# PCB_4.net
KiCad netlist of a schematic drawn in EAGLE
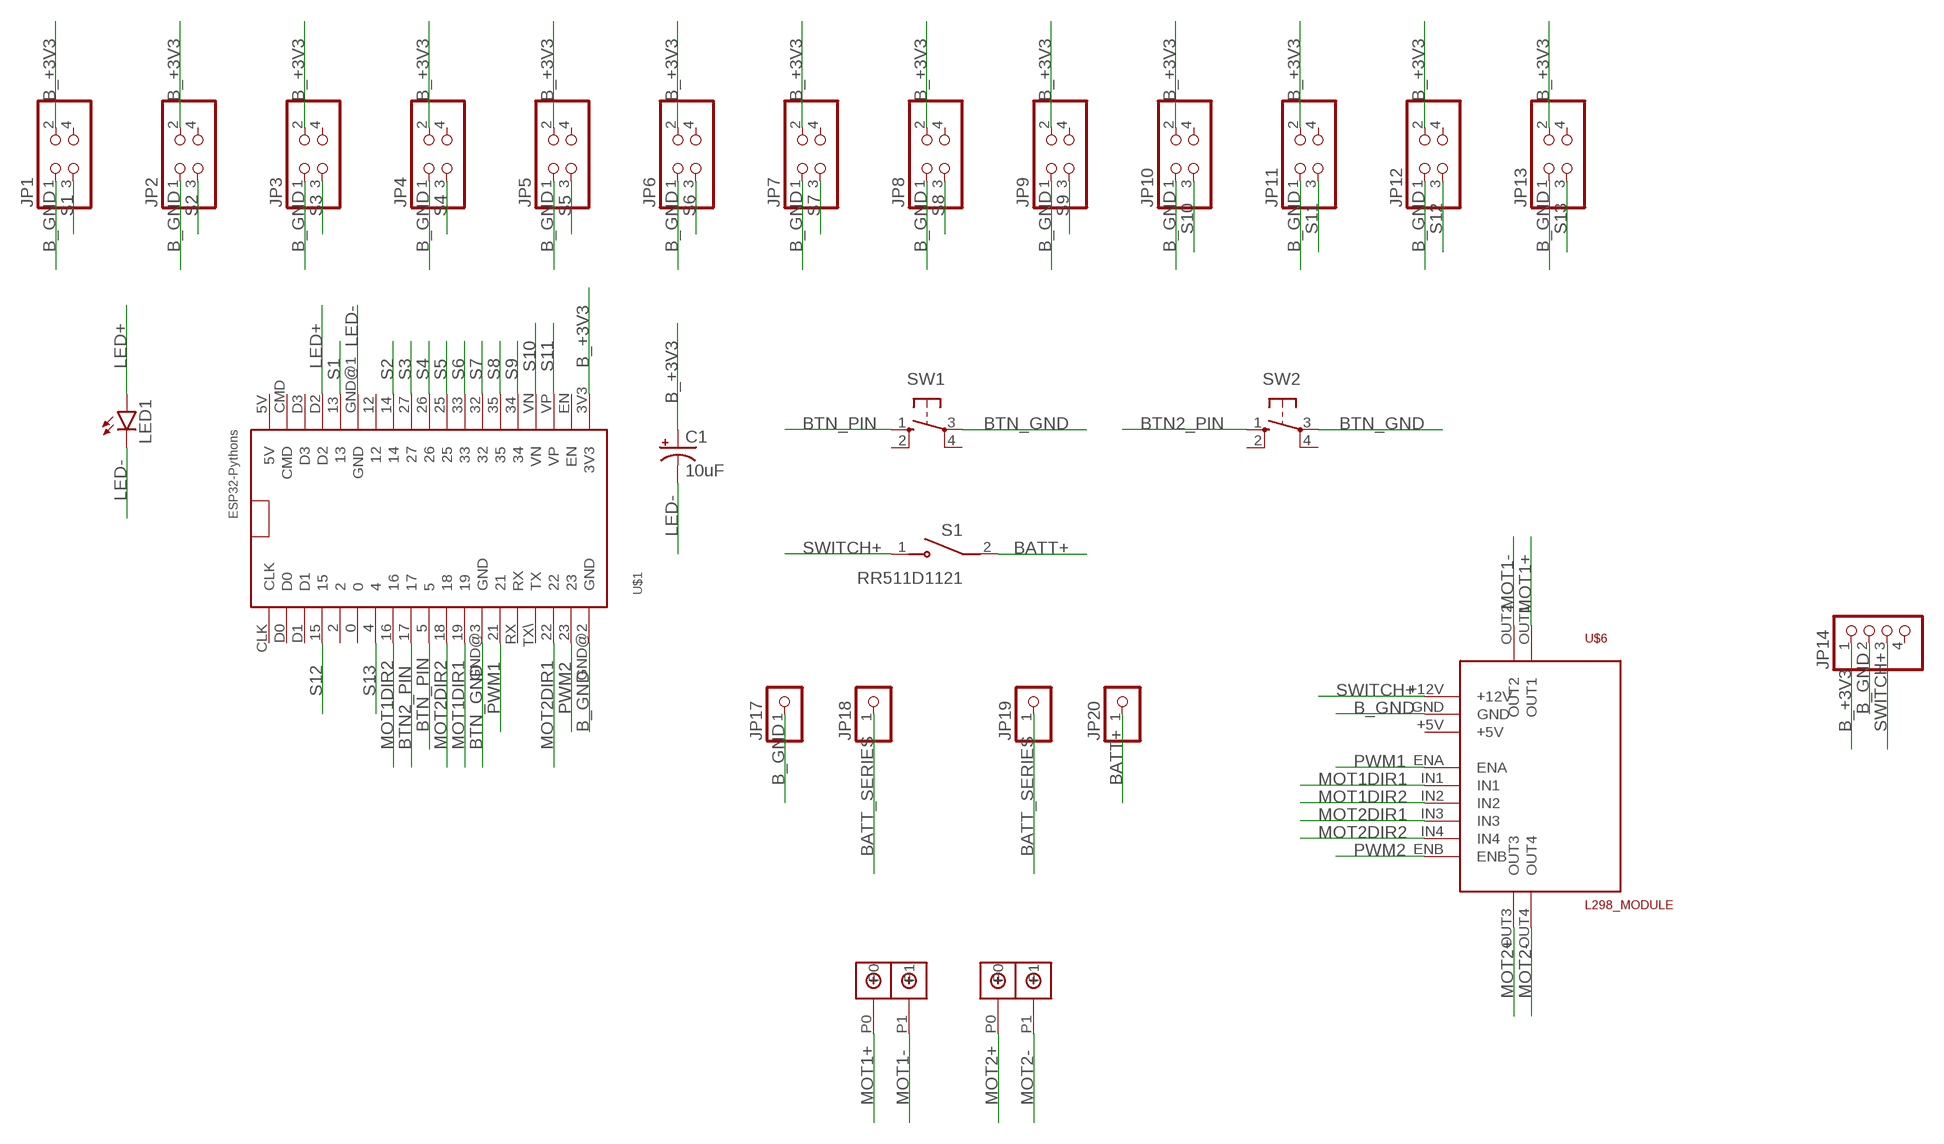
[diagram p0: schematic, sheet 1]

(export (version "E")
  (design (tool "Eeschema 10.0.6"))
  (components
    (comp (ref "C1")
      (value "10uF")
      (footprint "eagle-import:CPOL-RADIAL-2.5MM-5MM")
      (libsource (lib "eagle-import") (part "10UF-POLAR-RADIAL-2.5MM-25V-20%"))
    )
    (comp (ref "JP1")
      (value "PINHD-2X2")
      (footprint "eagle-import:2X02")
      (libsource (lib "eagle-import") (part "PINHD-2X2"))
    )
    (comp (ref "JP2")
      (value "PINHD-2X2")
      (footprint "eagle-import:2X02")
      (libsource (lib "eagle-import") (part "PINHD-2X2"))
    )
    (comp (ref "JP3")
      (value "PINHD-2X2")
      (footprint "eagle-import:2X02")
      (libsource (lib "eagle-import") (part "PINHD-2X2"))
    )
    (comp (ref "JP4")
      (value "PINHD-2X2")
      (footprint "eagle-import:2X02")
      (libsource (lib "eagle-import") (part "PINHD-2X2"))
    )
    (comp (ref "JP5")
      (value "PINHD-2X2")
      (footprint "eagle-import:2X02")
      (libsource (lib "eagle-import") (part "PINHD-2X2"))
    )
    (comp (ref "JP6")
      (value "PINHD-2X2")
      (footprint "eagle-import:2X02")
      (libsource (lib "eagle-import") (part "PINHD-2X2"))
    )
    (comp (ref "JP7")
      (value "PINHD-2X2")
      (footprint "eagle-import:2X02")
      (libsource (lib "eagle-import") (part "PINHD-2X2"))
    )
    (comp (ref "JP8")
      (value "PINHD-2X2")
      (footprint "eagle-import:2X02")
      (libsource (lib "eagle-import") (part "PINHD-2X2"))
    )
    (comp (ref "JP9")
      (value "PINHD-2X2")
      (footprint "eagle-import:2X02")
      (libsource (lib "eagle-import") (part "PINHD-2X2"))
    )
    (comp (ref "JP10")
      (value "PINHD-2X2")
      (footprint "eagle-import:2X02")
      (libsource (lib "eagle-import") (part "PINHD-2X2"))
    )
    (comp (ref "JP11")
      (value "PINHD-2X2")
      (footprint "eagle-import:2X02")
      (libsource (lib "eagle-import") (part "PINHD-2X2"))
    )
    (comp (ref "JP12")
      (value "PINHD-2X2")
      (footprint "eagle-import:2X02")
      (libsource (lib "eagle-import") (part "PINHD-2X2"))
    )
    (comp (ref "JP13")
      (value "PINHD-2X2")
      (footprint "eagle-import:2X02")
      (libsource (lib "eagle-import") (part "PINHD-2X2"))
    )
    (comp (ref "JP14")
      (value "PINHD-1X4")
      (footprint "eagle-import:1X04")
      (libsource (lib "eagle-import") (part "PINHD-1X4"))
    )
    (comp (ref "JP17")
      (value "PINHD-1X1")
      (footprint "eagle-import:1X01")
      (libsource (lib "eagle-import") (part "PINHD-1X1"))
    )
    (comp (ref "JP18")
      (value "PINHD-1X1")
      (footprint "eagle-import:1X01")
      (libsource (lib "eagle-import") (part "PINHD-1X1"))
    )
    (comp (ref "JP19")
      (value "PINHD-1X1")
      (footprint "eagle-import:1X01")
      (libsource (lib "eagle-import") (part "PINHD-1X1"))
    )
    (comp (ref "JP20")
      (value "PINHD-1X1")
      (footprint "eagle-import:1X01")
      (libsource (lib "eagle-import") (part "PINHD-1X1"))
    )
    (comp (ref "LED1")
      (value "LED5MM")
      (footprint "eagle-import:LED5MM")
      (libsource (lib "eagle-import") (part "LED5MM"))
    )
    (comp (ref "S1")
      (value "RR511D1121")
      (footprint "eagle-import:E-SWITCH_RR511D1121")
      (fields (field (name "MF") "E-Switch"))
      (libsource (lib "eagle-import") (part "RR511D1121"))
    )
    (comp (ref "SW1")
      (value "10-XX")
      (footprint "eagle-import:B3F-10XX")
      (libsource (lib "eagle-import") (part "10-XX"))
    )
    (comp (ref "SW2")
      (value "10-XX")
      (footprint "eagle-import:B3F-10XX")
      (libsource (lib "eagle-import") (part "10-XX"))
    )
    (comp (ref "U$1")
      (value "ESP32DEVKITV1")
      (footprint "eagle-import:ESP32-DEVKITV1")
      (libsource (lib "eagle-import") (part "ESP32DEVKITV1"))
    )
    (comp (ref "U$2")
      (value "DBCONN-1X2")
      (footprint "eagle-import:DBCONN-1X2")
      (libsource (lib "eagle-import") (part "DBCONN-1X2"))
    )
    (comp (ref "U$3")
      (value "DBCONN-1X2")
      (footprint "eagle-import:DBCONN-1X2")
      (libsource (lib "eagle-import") (part "DBCONN-1X2"))
    )
    (comp (ref "U$6")
      (value "L298_MODULE")
      (footprint "eagle-import:L298_MODULE")
      (libsource (lib "eagle-import") (part "L298_MODULE"))
    )
  )
  (nets
    (net (code "1") (name "/BATT+") (class "Default")
      (node (ref "JP20") (pin "1") (pinfunction "1_1") (pintype "passive"))
      (node (ref "S1") (pin "2") (pinfunction "COM_2") (pintype "passive"))
    )
    (net (code "2") (name "/BATT_SERIES") (class "Default")
      (node (ref "JP18") (pin "1") (pinfunction "1_1") (pintype "passive"))
      (node (ref "JP19") (pin "1") (pinfunction "1_1") (pintype "passive"))
    )
    (net (code "3") (name "/BTN2_PIN") (class "Default")
      (node (ref "SW2") (pin "1") (pinfunction "S_1") (pintype "passive"))
      (node (ref "U$1") (pin "17") (pinfunction "17_17") (pintype "bidirectional"))
    )
    (net (code "4") (name "/BTN_GND") (class "Default")
      (node (ref "SW1") (pin "3") (pinfunction "P_3") (pintype "passive"))
      (node (ref "SW2") (pin "3") (pinfunction "P_3") (pintype "passive"))
      (node (ref "U$1") (pin "GND@3") (pinfunction "GND_GND@3") (pintype "bidirectional"))
    )
    (net (code "5") (name "/BTN_PIN") (class "Default")
      (node (ref "SW1") (pin "1") (pinfunction "S_1") (pintype "passive"))
      (node (ref "U$1") (pin "5") (pinfunction "5_5") (pintype "bidirectional"))
    )
    (net (code "6") (name "/B_+3V3") (class "Default")
      (node (ref "C1") (pin "1") (pinfunction "+_1") (pintype "passive"))
      (node (ref "JP1") (pin "2") (pinfunction "2_2") (pintype "passive"))
      (node (ref "JP10") (pin "2") (pinfunction "2_2") (pintype "passive"))
      (node (ref "JP11") (pin "2") (pinfunction "2_2") (pintype "passive"))
      (node (ref "JP12") (pin "2") (pinfunction "2_2") (pintype "passive"))
      (node (ref "JP13") (pin "2") (pinfunction "2_2") (pintype "passive"))
      (node (ref "JP14") (pin "1") (pinfunction "1_1") (pintype "passive"))
      (node (ref "JP2") (pin "2") (pinfunction "2_2") (pintype "passive"))
      (node (ref "JP3") (pin "2") (pinfunction "2_2") (pintype "passive"))
      (node (ref "JP4") (pin "2") (pinfunction "2_2") (pintype "passive"))
      (node (ref "JP5") (pin "2") (pinfunction "2_2") (pintype "passive"))
      (node (ref "JP6") (pin "2") (pinfunction "2_2") (pintype "passive"))
      (node (ref "JP7") (pin "2") (pinfunction "2_2") (pintype "passive"))
      (node (ref "JP8") (pin "2") (pinfunction "2_2") (pintype "passive"))
      (node (ref "JP9") (pin "2") (pinfunction "2_2") (pintype "passive"))
      (node (ref "U$1") (pin "3V3") (pinfunction "3V3_3V3") (pintype "bidirectional"))
    )
    (net (code "7") (name "/B_GND") (class "Default")
      (node (ref "JP1") (pin "1") (pinfunction "1_1") (pintype "passive"))
      (node (ref "JP10") (pin "1") (pinfunction "1_1") (pintype "passive"))
      (node (ref "JP11") (pin "1") (pinfunction "1_1") (pintype "passive"))
      (node (ref "JP12") (pin "1") (pinfunction "1_1") (pintype "passive"))
      (node (ref "JP13") (pin "1") (pinfunction "1_1") (pintype "passive"))
      (node (ref "JP14") (pin "2") (pinfunction "2_2") (pintype "passive"))
      (node (ref "JP17") (pin "1") (pinfunction "1_1") (pintype "passive"))
      (node (ref "JP2") (pin "1") (pinfunction "1_1") (pintype "passive"))
      (node (ref "JP3") (pin "1") (pinfunction "1_1") (pintype "passive"))
      (node (ref "JP4") (pin "1") (pinfunction "1_1") (pintype "passive"))
      (node (ref "JP5") (pin "1") (pinfunction "1_1") (pintype "passive"))
      (node (ref "JP6") (pin "1") (pinfunction "1_1") (pintype "passive"))
      (node (ref "JP7") (pin "1") (pinfunction "1_1") (pintype "passive"))
      (node (ref "JP8") (pin "1") (pinfunction "1_1") (pintype "passive"))
      (node (ref "JP9") (pin "1") (pinfunction "1_1") (pintype "passive"))
      (node (ref "U$1") (pin "GND@2") (pinfunction "GND_GND@2") (pintype "bidirectional"))
      (node (ref "U$6") (pin "GND") (pinfunction "GND_GND") (pintype "bidirectional"))
    )
    (net (code "8") (name "/LED+") (class "Default")
      (node (ref "LED1") (pin "A") (pinfunction "A_A") (pintype "passive"))
      (node (ref "U$1") (pin "D2") (pinfunction "D2_D2") (pintype "bidirectional"))
    )
    (net (code "9") (name "/LED-") (class "Default")
      (node (ref "C1") (pin "2") (pinfunction "-_2") (pintype "passive"))
      (node (ref "LED1") (pin "K") (pinfunction "C_K") (pintype "passive"))
      (node (ref "U$1") (pin "GND@1") (pinfunction "GND_GND@1") (pintype "bidirectional"))
    )
    (net (code "10") (name "/MOT1+") (class "Default")
      (node (ref "U$2") (pin "P0") (pinfunction "P0_P0") (pintype "bidirectional"))
      (node (ref "U$6") (pin "OUT1") (pinfunction "OUT1_OUT1") (pintype "bidirectional"))
    )
    (net (code "11") (name "/MOT1-") (class "Default")
      (node (ref "U$2") (pin "P1") (pinfunction "P1_P1") (pintype "bidirectional"))
      (node (ref "U$6") (pin "OUT2") (pinfunction "OUT2_OUT2") (pintype "bidirectional"))
    )
    (net (code "12") (name "/MOT1DIR1") (class "Default")
      (node (ref "U$1") (pin "19") (pinfunction "19_19") (pintype "bidirectional"))
      (node (ref "U$6") (pin "IN1") (pinfunction "IN1_IN1") (pintype "bidirectional"))
    )
    (net (code "13") (name "/MOT1DIR2") (class "Default")
      (node (ref "U$1") (pin "16") (pinfunction "16_16") (pintype "bidirectional"))
      (node (ref "U$6") (pin "IN2") (pinfunction "IN2_IN2") (pintype "bidirectional"))
    )
    (net (code "14") (name "/MOT2+") (class "Default")
      (node (ref "U$3") (pin "P0") (pinfunction "P0_P0") (pintype "bidirectional"))
      (node (ref "U$6") (pin "OUT3") (pinfunction "OUT3_OUT3") (pintype "bidirectional"))
    )
    (net (code "15") (name "/MOT2-") (class "Default")
      (node (ref "U$3") (pin "P1") (pinfunction "P1_P1") (pintype "bidirectional"))
      (node (ref "U$6") (pin "OUT4") (pinfunction "OUT4_OUT4") (pintype "bidirectional"))
    )
    (net (code "16") (name "/MOT2DIR1") (class "Default")
      (node (ref "U$1") (pin "22") (pinfunction "22_22") (pintype "bidirectional"))
      (node (ref "U$6") (pin "IN3") (pinfunction "IN3_IN3") (pintype "bidirectional"))
    )
    (net (code "17") (name "/MOT2DIR2") (class "Default")
      (node (ref "U$1") (pin "18") (pinfunction "18_18") (pintype "bidirectional"))
      (node (ref "U$6") (pin "IN4") (pinfunction "IN4_IN4") (pintype "bidirectional"))
    )
    (net (code "18") (name "/PWM1") (class "Default")
      (node (ref "U$1") (pin "21") (pinfunction "21_21") (pintype "bidirectional"))
      (node (ref "U$6") (pin "ENA") (pinfunction "ENA_ENA") (pintype "bidirectional"))
    )
    (net (code "19") (name "/PWM2") (class "Default")
      (node (ref "U$1") (pin "23") (pinfunction "23_23") (pintype "bidirectional"))
      (node (ref "U$6") (pin "ENB") (pinfunction "ENB_ENB") (pintype "bidirectional"))
    )
    (net (code "20") (name "/S1") (class "Default")
      (node (ref "JP1") (pin "3") (pinfunction "3_3") (pintype "passive"))
      (node (ref "U$1") (pin "13") (pinfunction "13_13") (pintype "bidirectional"))
    )
    (net (code "21") (name "/S2") (class "Default")
      (node (ref "JP2") (pin "3") (pinfunction "3_3") (pintype "passive"))
      (node (ref "U$1") (pin "14") (pinfunction "14_14") (pintype "bidirectional"))
    )
    (net (code "22") (name "/S3") (class "Default")
      (node (ref "JP3") (pin "3") (pinfunction "3_3") (pintype "passive"))
      (node (ref "U$1") (pin "27") (pinfunction "27_27") (pintype "bidirectional"))
    )
    (net (code "23") (name "/S4") (class "Default")
      (node (ref "JP4") (pin "3") (pinfunction "3_3") (pintype "passive"))
      (node (ref "U$1") (pin "26") (pinfunction "26_26") (pintype "bidirectional"))
    )
    (net (code "24") (name "/S5") (class "Default")
      (node (ref "JP5") (pin "3") (pinfunction "3_3") (pintype "passive"))
      (node (ref "U$1") (pin "25") (pinfunction "25_25") (pintype "bidirectional"))
    )
    (net (code "25") (name "/S6") (class "Default")
      (node (ref "JP6") (pin "3") (pinfunction "3_3") (pintype "passive"))
      (node (ref "U$1") (pin "33") (pinfunction "33_33") (pintype "bidirectional"))
    )
    (net (code "26") (name "/S7") (class "Default")
      (node (ref "JP7") (pin "3") (pinfunction "3_3") (pintype "passive"))
      (node (ref "U$1") (pin "32") (pinfunction "32_32") (pintype "bidirectional"))
    )
    (net (code "27") (name "/S8") (class "Default")
      (node (ref "JP8") (pin "3") (pinfunction "3_3") (pintype "passive"))
      (node (ref "U$1") (pin "35") (pinfunction "35_35") (pintype "bidirectional"))
    )
    (net (code "28") (name "/S9") (class "Default")
      (node (ref "JP9") (pin "3") (pinfunction "3_3") (pintype "passive"))
      (node (ref "U$1") (pin "34") (pinfunction "34_34") (pintype "bidirectional"))
    )
    (net (code "29") (name "/S10") (class "Default")
      (node (ref "JP10") (pin "3") (pinfunction "3_3") (pintype "passive"))
      (node (ref "U$1") (pin "VN") (pinfunction "VN_VN") (pintype "bidirectional"))
    )
    (net (code "30") (name "/S11") (class "Default")
      (node (ref "JP11") (pin "3") (pinfunction "3_3") (pintype "passive"))
      (node (ref "U$1") (pin "VP") (pinfunction "VP_VP") (pintype "bidirectional"))
    )
    (net (code "31") (name "/S12") (class "Default")
      (node (ref "JP12") (pin "3") (pinfunction "3_3") (pintype "passive"))
      (node (ref "U$1") (pin "15") (pinfunction "15_15") (pintype "bidirectional"))
    )
    (net (code "32") (name "/S13") (class "Default")
      (node (ref "JP13") (pin "3") (pinfunction "3_3") (pintype "passive"))
      (node (ref "U$1") (pin "4") (pinfunction "4_4") (pintype "bidirectional"))
    )
    (net (code "33") (name "/SWITCH+") (class "Default")
      (node (ref "JP14") (pin "3") (pinfunction "3_3") (pintype "passive"))
      (node (ref "S1") (pin "1") (pinfunction "NO_1") (pintype "passive"))
      (node (ref "U$6") (pin "+12V") (pinfunction "+12V_+12V") (pintype "bidirectional"))
    )
    (net (code "34") (name "unconnected-(JP1-Pad4)") (class "Default")
      (node (ref "JP1") (pin "4") (pinfunction "4_4") (pintype "passive"))
    )
    (net (code "35") (name "unconnected-(JP2-Pad4)") (class "Default")
      (node (ref "JP2") (pin "4") (pinfunction "4_4") (pintype "passive"))
    )
    (net (code "36") (name "unconnected-(JP3-Pad4)") (class "Default")
      (node (ref "JP3") (pin "4") (pinfunction "4_4") (pintype "passive"))
    )
    (net (code "37") (name "unconnected-(JP4-Pad4)") (class "Default")
      (node (ref "JP4") (pin "4") (pinfunction "4_4") (pintype "passive"))
    )
    (net (code "38") (name "unconnected-(JP5-Pad4)") (class "Default")
      (node (ref "JP5") (pin "4") (pinfunction "4_4") (pintype "passive"))
    )
    (net (code "39") (name "unconnected-(JP6-Pad4)") (class "Default")
      (node (ref "JP6") (pin "4") (pinfunction "4_4") (pintype "passive"))
    )
    (net (code "40") (name "unconnected-(JP7-Pad4)") (class "Default")
      (node (ref "JP7") (pin "4") (pinfunction "4_4") (pintype "passive"))
    )
    (net (code "41") (name "unconnected-(JP8-Pad4)") (class "Default")
      (node (ref "JP8") (pin "4") (pinfunction "4_4") (pintype "passive"))
    )
    (net (code "42") (name "unconnected-(JP9-Pad4)") (class "Default")
      (node (ref "JP9") (pin "4") (pinfunction "4_4") (pintype "passive"))
    )
    (net (code "43") (name "unconnected-(JP10-Pad4)") (class "Default")
      (node (ref "JP10") (pin "4") (pinfunction "4_4") (pintype "passive"))
    )
    (net (code "44") (name "unconnected-(JP11-Pad4)") (class "Default")
      (node (ref "JP11") (pin "4") (pinfunction "4_4") (pintype "passive"))
    )
    (net (code "45") (name "unconnected-(JP12-Pad4)") (class "Default")
      (node (ref "JP12") (pin "4") (pinfunction "4_4") (pintype "passive"))
    )
    (net (code "46") (name "unconnected-(JP13-Pad4)") (class "Default")
      (node (ref "JP13") (pin "4") (pinfunction "4_4") (pintype "passive"))
    )
    (net (code "47") (name "unconnected-(JP14-Pad4)") (class "Default")
      (node (ref "JP14") (pin "4") (pinfunction "4_4") (pintype "passive"))
    )
    (net (code "48") (name "unconnected-(SW1-P1-Pad4)") (class "Default")
      (node (ref "SW1") (pin "4") (pinfunction "P1_4") (pintype "passive"))
    )
    (net (code "49") (name "unconnected-(SW1-S1-Pad2)") (class "Default")
      (node (ref "SW1") (pin "2") (pinfunction "S1_2") (pintype "passive"))
    )
    (net (code "50") (name "unconnected-(SW2-P1-Pad4)") (class "Default")
      (node (ref "SW2") (pin "4") (pinfunction "P1_4") (pintype "passive"))
    )
    (net (code "51") (name "unconnected-(SW2-S1-Pad2)") (class "Default")
      (node (ref "SW2") (pin "2") (pinfunction "S1_2") (pintype "passive"))
    )
    (net (code "52") (name "unconnected-(U$1-Pad0)") (class "Default")
      (node (ref "U$1") (pin "0") (pinfunction "0_0") (pintype "bidirectional"))
    )
    (net (code "53") (name "unconnected-(U$1-Pad2)") (class "Default")
      (node (ref "U$1") (pin "2") (pinfunction "2_2") (pintype "bidirectional"))
    )
    (net (code "54") (name "unconnected-(U$1-Pad5V)") (class "Default")
      (node (ref "U$1") (pin "5V") (pinfunction "5V_5V") (pintype "bidirectional"))
    )
    (net (code "55") (name "unconnected-(U$1-Pad12)") (class "Default")
      (node (ref "U$1") (pin "12") (pinfunction "12_12") (pintype "bidirectional"))
    )
    (net (code "56") (name "unconnected-(U$1-PadCLK)") (class "Default")
      (node (ref "U$1") (pin "CLK") (pinfunction "CLK_CLK") (pintype "bidirectional"))
    )
    (net (code "57") (name "unconnected-(U$1-PadCMD)") (class "Default")
      (node (ref "U$1") (pin "CMD") (pinfunction "CMD_CMD") (pintype "bidirectional"))
    )
    (net (code "58") (name "unconnected-(U$1-PadD0)") (class "Default")
      (node (ref "U$1") (pin "D0") (pinfunction "D0_D0") (pintype "bidirectional"))
    )
    (net (code "59") (name "unconnected-(U$1-PadD1)") (class "Default")
      (node (ref "U$1") (pin "D1") (pinfunction "D1_D1") (pintype "bidirectional"))
    )
    (net (code "60") (name "unconnected-(U$1-PadD3)") (class "Default")
      (node (ref "U$1") (pin "D3") (pinfunction "D3_D3") (pintype "bidirectional"))
    )
    (net (code "61") (name "unconnected-(U$1-PadEN)") (class "Default")
      (node (ref "U$1") (pin "EN") (pinfunction "EN_EN") (pintype "bidirectional"))
    )
    (net (code "62") (name "unconnected-(U$1-PadRX)") (class "Default")
      (node (ref "U$1") (pin "RX") (pinfunction "RX_RX") (pintype "bidirectional"))
    )
    (net (code "63") (name "unconnected-(U$1-TX-PadTX\\)") (class "Default")
      (node (ref "U$1") (pin "TX\\") (pinfunction "TX_TX\\") (pintype "bidirectional"))
    )
    (net (code "64") (name "unconnected-(U$6-Pad+5V)") (class "Default")
      (node (ref "U$6") (pin "+5V") (pinfunction "+5V_+5V") (pintype "bidirectional"))
    )
  )
)
